# tim_encoder.net
KiCad netlist of a schematic drawn in EAGLE
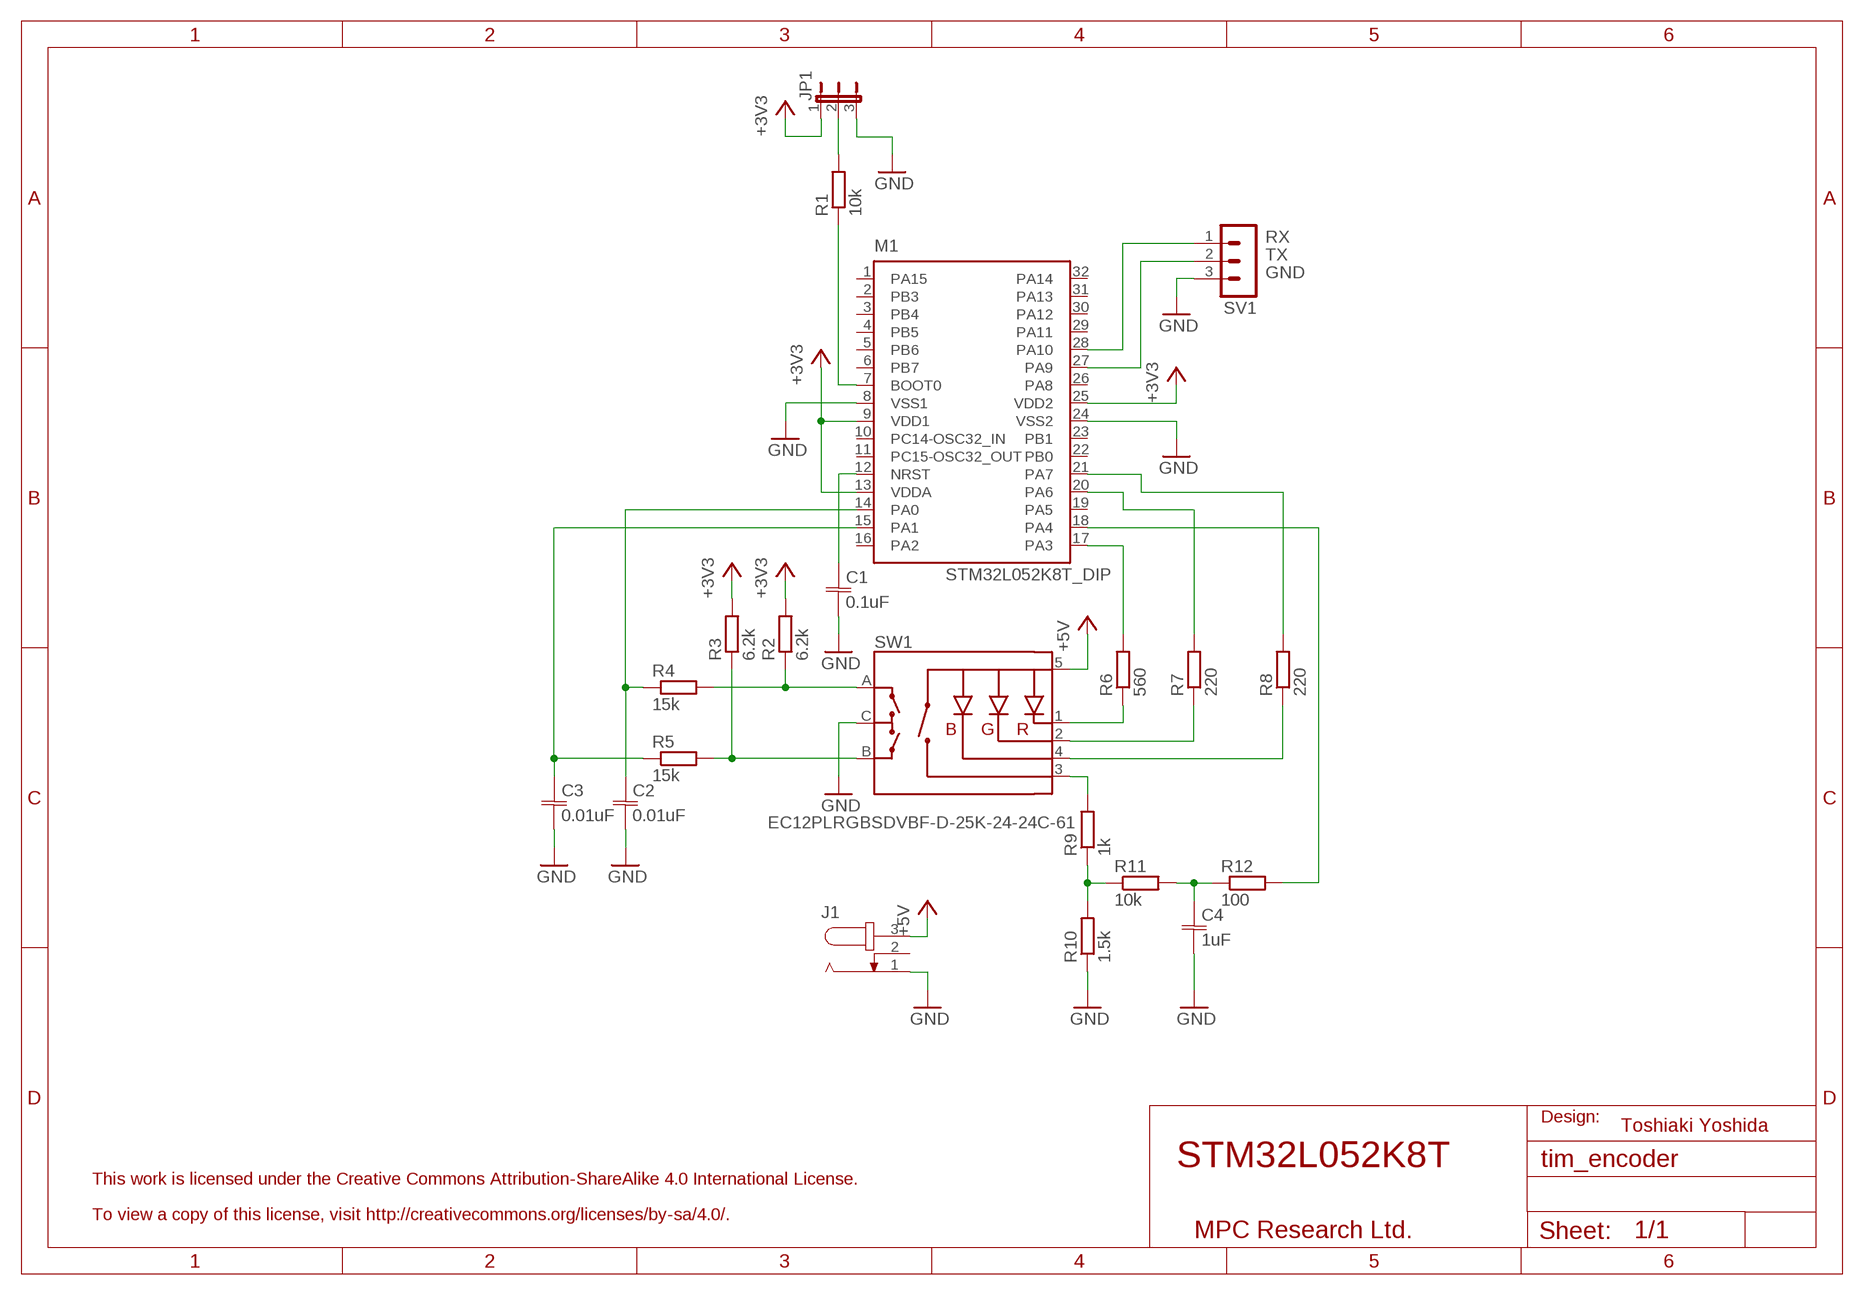
[diagram p0: schematic, sheet 1]

(export (version "E")
  (design (tool "Eeschema 10.0.6"))
  (components
    (comp (ref "C1")
      (value "0.1uF")
      (footprint "eagle-import:C050-024X044")
      (libsource (lib "eagle-import") (part "C-JIS050-024X044"))
    )
    (comp (ref "C2")
      (value "0.01uF")
      (footprint "eagle-import:C050-024X044")
      (libsource (lib "eagle-import") (part "C-JIS050-024X044"))
    )
    (comp (ref "C3")
      (value "0.01uF")
      (footprint "eagle-import:C050-024X044")
      (libsource (lib "eagle-import") (part "C-JIS050-024X044"))
    )
    (comp (ref "C4")
      (value "1uF")
      (footprint "eagle-import:C050-024X044")
      (libsource (lib "eagle-import") (part "C-JIS050-024X044"))
    )
    (comp (ref "J1")
      (value "JACK-PLUG0")
      (footprint "eagle-import:SPC4077")
      (libsource (lib "eagle-import") (part "JACK-PLUG0"))
    )
    (comp (ref "JP1")
      (value "JP2E")
      (footprint "eagle-import:JP2")
      (libsource (lib "eagle-import") (part "JP2E"))
    )
    (comp (ref "M1")
      (value "STM32L052K8T_DIP")
      (footprint "eagle-import:DIP32")
      (libsource (lib "eagle-import") (part "STM32L052K8T_DIP"))
    )
    (comp (ref "R1")
      (value "10k")
      (footprint "eagle-import:0207_2V")
      (libsource (lib "eagle-import") (part "R-EU_0207/2V"))
    )
    (comp (ref "R2")
      (value "6.2k")
      (footprint "eagle-import:0207_2V")
      (libsource (lib "eagle-import") (part "R-EU_0207/2V"))
    )
    (comp (ref "R3")
      (value "6.2k")
      (footprint "eagle-import:0207_2V")
      (libsource (lib "eagle-import") (part "R-EU_0207/2V"))
    )
    (comp (ref "R4")
      (value "15k")
      (footprint "eagle-import:0207_2V")
      (libsource (lib "eagle-import") (part "R-EU_0207/2V"))
    )
    (comp (ref "R5")
      (value "15k")
      (footprint "eagle-import:0207_2V")
      (libsource (lib "eagle-import") (part "R-EU_0207/2V"))
    )
    (comp (ref "R6")
      (value "560")
      (footprint "eagle-import:0207_2V")
      (libsource (lib "eagle-import") (part "R-EU_0207/2V"))
    )
    (comp (ref "R7")
      (value "220")
      (footprint "eagle-import:0207_2V")
      (libsource (lib "eagle-import") (part "R-EU_0207/2V"))
    )
    (comp (ref "R8")
      (value "220")
      (footprint "eagle-import:0207_2V")
      (libsource (lib "eagle-import") (part "R-EU_0207/2V"))
    )
    (comp (ref "R9")
      (value "1k")
      (footprint "eagle-import:0207_2V")
      (libsource (lib "eagle-import") (part "R-EU_0207/2V"))
    )
    (comp (ref "R10")
      (value "1.5k")
      (footprint "eagle-import:0207_2V")
      (libsource (lib "eagle-import") (part "R-EU_0207/2V"))
    )
    (comp (ref "R11")
      (value "10k")
      (footprint "eagle-import:0207_2V")
      (libsource (lib "eagle-import") (part "R-EU_0207/2V"))
    )
    (comp (ref "R12")
      (value "100")
      (footprint "eagle-import:0207_2V")
      (libsource (lib "eagle-import") (part "R-EU_0207/2V"))
    )
    (comp (ref "SV1")
      (value "MA03-1")
      (footprint "eagle-import:MA03-1")
      (libsource (lib "eagle-import") (part "MA03-1"))
    )
    (comp (ref "SW1")
      (value "EC12PLRGBSDVBF-D-25K-24-24C-61")
      (footprint "eagle-import:ENCODER_LED_3")
      (libsource (lib "eagle-import") (part "ENCODER_RGB_CA"))
    )
  )
  (nets
    (net (code "1") (name "+3V3") (class "Default")
      (node (ref "JP1") (pin "1") (pinfunction "1_1") (pintype "passive"))
      (node (ref "M1") (pin "13") (pinfunction "VDDA_13") (pintype "power_in"))
      (node (ref "M1") (pin "25") (pinfunction "VDD2_25") (pintype "bidirectional"))
      (node (ref "M1") (pin "9") (pinfunction "VDD1_9") (pintype "power_in"))
      (node (ref "R2") (pin "2") (pinfunction "2_2") (pintype "passive"))
      (node (ref "R3") (pin "2") (pinfunction "2_2") (pintype "passive"))
    )
    (net (code "2") (name "+5V") (class "Default")
      (node (ref "J1") (pin "3") (pinfunction "3_3") (pintype "passive"))
      (node (ref "SW1") (pin "5") (pinfunction "+_5") (pintype "passive"))
    )
    (net (code "3") (name "GND") (class "Default")
      (node (ref "C1") (pin "2") (pinfunction "2_2") (pintype "passive"))
      (node (ref "C2") (pin "2") (pinfunction "2_2") (pintype "passive"))
      (node (ref "C3") (pin "2") (pinfunction "2_2") (pintype "passive"))
      (node (ref "C4") (pin "2") (pinfunction "2_2") (pintype "passive"))
      (node (ref "J1") (pin "1") (pinfunction "1_1") (pintype "passive"))
      (node (ref "JP1") (pin "3") (pinfunction "3_3") (pintype "passive"))
      (node (ref "M1") (pin "24") (pinfunction "VSS2_24") (pintype "power_in"))
      (node (ref "M1") (pin "8") (pinfunction "VSS1_8") (pintype "power_in"))
      (node (ref "R10") (pin "1") (pinfunction "1_1") (pintype "passive"))
      (node (ref "SV1") (pin "3") (pinfunction "3_3") (pintype "passive"))
      (node (ref "SW1") (pin "C") (pinfunction "C_C") (pintype "bidirectional"))
    )
    (net (code "4") (name "Net-(C4-Pad1)") (class "Default")
      (node (ref "C4") (pin "1") (pinfunction "1_1") (pintype "passive"))
      (node (ref "R11") (pin "2") (pinfunction "2_2") (pintype "passive"))
      (node (ref "R12") (pin "1") (pinfunction "1_1") (pintype "passive"))
    )
    (net (code "5") (name "Net-(JP1-Pad2)") (class "Default")
      (node (ref "JP1") (pin "2") (pinfunction "2_2") (pintype "passive"))
      (node (ref "R1") (pin "2") (pinfunction "2_2") (pintype "passive"))
    )
    (net (code "6") (name "Net-(M1-BOOT0)") (class "Default")
      (node (ref "M1") (pin "7") (pinfunction "BOOT0_7") (pintype "bidirectional"))
      (node (ref "R1") (pin "1") (pinfunction "1_1") (pintype "passive"))
    )
    (net (code "7") (name "Net-(M1-NRST)") (class "Default")
      (node (ref "C1") (pin "1") (pinfunction "1_1") (pintype "passive"))
      (node (ref "M1") (pin "12") (pinfunction "NRST_12") (pintype "bidirectional"))
    )
    (net (code "8") (name "Net-(M1-PA0)") (class "Default")
      (node (ref "C2") (pin "1") (pinfunction "1_1") (pintype "passive"))
      (node (ref "M1") (pin "14") (pinfunction "PA0_14") (pintype "bidirectional"))
      (node (ref "R4") (pin "1") (pinfunction "1_1") (pintype "passive"))
    )
    (net (code "9") (name "Net-(M1-PA1)") (class "Default")
      (node (ref "C3") (pin "1") (pinfunction "1_1") (pintype "passive"))
      (node (ref "M1") (pin "15") (pinfunction "PA1_15") (pintype "bidirectional"))
      (node (ref "R5") (pin "1") (pinfunction "1_1") (pintype "passive"))
    )
    (net (code "10") (name "Net-(M1-PA3)") (class "Default")
      (node (ref "M1") (pin "17") (pinfunction "PA3_17") (pintype "bidirectional"))
      (node (ref "R6") (pin "2") (pinfunction "2_2") (pintype "passive"))
    )
    (net (code "11") (name "Net-(M1-PA4)") (class "Default")
      (node (ref "M1") (pin "18") (pinfunction "PA4_18") (pintype "bidirectional"))
      (node (ref "R12") (pin "2") (pinfunction "2_2") (pintype "passive"))
    )
    (net (code "12") (name "Net-(M1-PA6)") (class "Default")
      (node (ref "M1") (pin "20") (pinfunction "PA6_20") (pintype "bidirectional"))
      (node (ref "R7") (pin "2") (pinfunction "2_2") (pintype "passive"))
    )
    (net (code "13") (name "Net-(M1-PA7)") (class "Default")
      (node (ref "M1") (pin "21") (pinfunction "PA7_21") (pintype "bidirectional"))
      (node (ref "R8") (pin "2") (pinfunction "2_2") (pintype "passive"))
    )
    (net (code "14") (name "Net-(M1-PA9)") (class "Default")
      (node (ref "M1") (pin "27") (pinfunction "PA9_27") (pintype "bidirectional"))
      (node (ref "SV1") (pin "2") (pinfunction "2_2") (pintype "passive"))
    )
    (net (code "15") (name "Net-(M1-PA10)") (class "Default")
      (node (ref "M1") (pin "28") (pinfunction "PA10_28") (pintype "bidirectional"))
      (node (ref "SV1") (pin "1") (pinfunction "1_1") (pintype "passive"))
    )
    (net (code "16") (name "Net-(R2-Pad1)") (class "Default")
      (node (ref "R2") (pin "1") (pinfunction "1_1") (pintype "passive"))
      (node (ref "R4") (pin "2") (pinfunction "2_2") (pintype "passive"))
      (node (ref "SW1") (pin "A") (pinfunction "A_A") (pintype "bidirectional"))
    )
    (net (code "17") (name "Net-(R3-Pad1)") (class "Default")
      (node (ref "R3") (pin "1") (pinfunction "1_1") (pintype "passive"))
      (node (ref "R5") (pin "2") (pinfunction "2_2") (pintype "passive"))
      (node (ref "SW1") (pin "B") (pinfunction "B_B") (pintype "bidirectional"))
    )
    (net (code "18") (name "Net-(R10-Pad2)") (class "Default")
      (node (ref "R10") (pin "2") (pinfunction "2_2") (pintype "passive"))
      (node (ref "R11") (pin "1") (pinfunction "1_1") (pintype "passive"))
      (node (ref "R9") (pin "1") (pinfunction "1_1") (pintype "passive"))
    )
    (net (code "19") (name "Net-(SW1--B)") (class "Default")
      (node (ref "R8") (pin "1") (pinfunction "1_1") (pintype "passive"))
      (node (ref "SW1") (pin "4") (pinfunction "-B_4") (pintype "passive"))
    )
    (net (code "20") (name "Net-(SW1--G)") (class "Default")
      (node (ref "R7") (pin "1") (pinfunction "1_1") (pintype "passive"))
      (node (ref "SW1") (pin "2") (pinfunction "-G_2") (pintype "passive"))
    )
    (net (code "21") (name "Net-(SW1--R)") (class "Default")
      (node (ref "R6") (pin "1") (pinfunction "1_1") (pintype "passive"))
      (node (ref "SW1") (pin "1") (pinfunction "-R_1") (pintype "passive"))
    )
    (net (code "22") (name "Net-(SW1-SW)") (class "Default")
      (node (ref "R9") (pin "2") (pinfunction "2_2") (pintype "passive"))
      (node (ref "SW1") (pin "3") (pinfunction "SW_3") (pintype "passive"))
    )
    (net (code "23") (name "unconnected-(J1-Pad2)") (class "Default")
      (node (ref "J1") (pin "2") (pinfunction "2_2") (pintype "passive"))
    )
    (net (code "24") (name "unconnected-(M1-PA2-Pad16)") (class "Default")
      (node (ref "M1") (pin "16") (pinfunction "PA2_16") (pintype "bidirectional"))
    )
    (net (code "25") (name "unconnected-(M1-PA5-Pad19)") (class "Default")
      (node (ref "M1") (pin "19") (pinfunction "PA5_19") (pintype "bidirectional"))
    )
    (net (code "26") (name "unconnected-(M1-PA8-Pad26)") (class "Default")
      (node (ref "M1") (pin "26") (pinfunction "PA8_26") (pintype "bidirectional"))
    )
    (net (code "27") (name "unconnected-(M1-PA11-Pad29)") (class "Default")
      (node (ref "M1") (pin "29") (pinfunction "PA11_29") (pintype "bidirectional"))
    )
    (net (code "28") (name "unconnected-(M1-PA12-Pad30)") (class "Default")
      (node (ref "M1") (pin "30") (pinfunction "PA12_30") (pintype "bidirectional"))
    )
    (net (code "29") (name "unconnected-(M1-PA13-Pad31)") (class "Default")
      (node (ref "M1") (pin "31") (pinfunction "PA13_31") (pintype "bidirectional"))
    )
    (net (code "30") (name "unconnected-(M1-PA14-Pad32)") (class "Default")
      (node (ref "M1") (pin "32") (pinfunction "PA14_32") (pintype "bidirectional"))
    )
    (net (code "31") (name "unconnected-(M1-PA15-Pad1)") (class "Default")
      (node (ref "M1") (pin "1") (pinfunction "PA15_1") (pintype "bidirectional"))
    )
    (net (code "32") (name "unconnected-(M1-PB0-Pad22)") (class "Default")
      (node (ref "M1") (pin "22") (pinfunction "PB0_22") (pintype "bidirectional"))
    )
    (net (code "33") (name "unconnected-(M1-PB1-Pad23)") (class "Default")
      (node (ref "M1") (pin "23") (pinfunction "PB1_23") (pintype "bidirectional"))
    )
    (net (code "34") (name "unconnected-(M1-PB3-Pad2)") (class "Default")
      (node (ref "M1") (pin "2") (pinfunction "PB3_2") (pintype "bidirectional"))
    )
    (net (code "35") (name "unconnected-(M1-PB4-Pad3)") (class "Default")
      (node (ref "M1") (pin "3") (pinfunction "PB4_3") (pintype "bidirectional"))
    )
    (net (code "36") (name "unconnected-(M1-PB5-Pad4)") (class "Default")
      (node (ref "M1") (pin "4") (pinfunction "PB5_4") (pintype "bidirectional"))
    )
    (net (code "37") (name "unconnected-(M1-PB6-Pad5)") (class "Default")
      (node (ref "M1") (pin "5") (pinfunction "PB6_5") (pintype "bidirectional"))
    )
    (net (code "38") (name "unconnected-(M1-PB7-Pad6)") (class "Default")
      (node (ref "M1") (pin "6") (pinfunction "PB7_6") (pintype "bidirectional"))
    )
    (net (code "39") (name "unconnected-(M1-PC14-OSC32_IN-Pad10)") (class "Default")
      (node (ref "M1") (pin "10") (pinfunction "PC14-OSC32_IN_10") (pintype "bidirectional"))
    )
    (net (code "40") (name "unconnected-(M1-PC15-OSC32_OUT-Pad11)") (class "Default")
      (node (ref "M1") (pin "11") (pinfunction "PC15-OSC32_OUT_11") (pintype "bidirectional"))
    )
  )
)
